# CircuitClockAutorouted.net
KiCad netlist of a schematic drawn in EAGLE
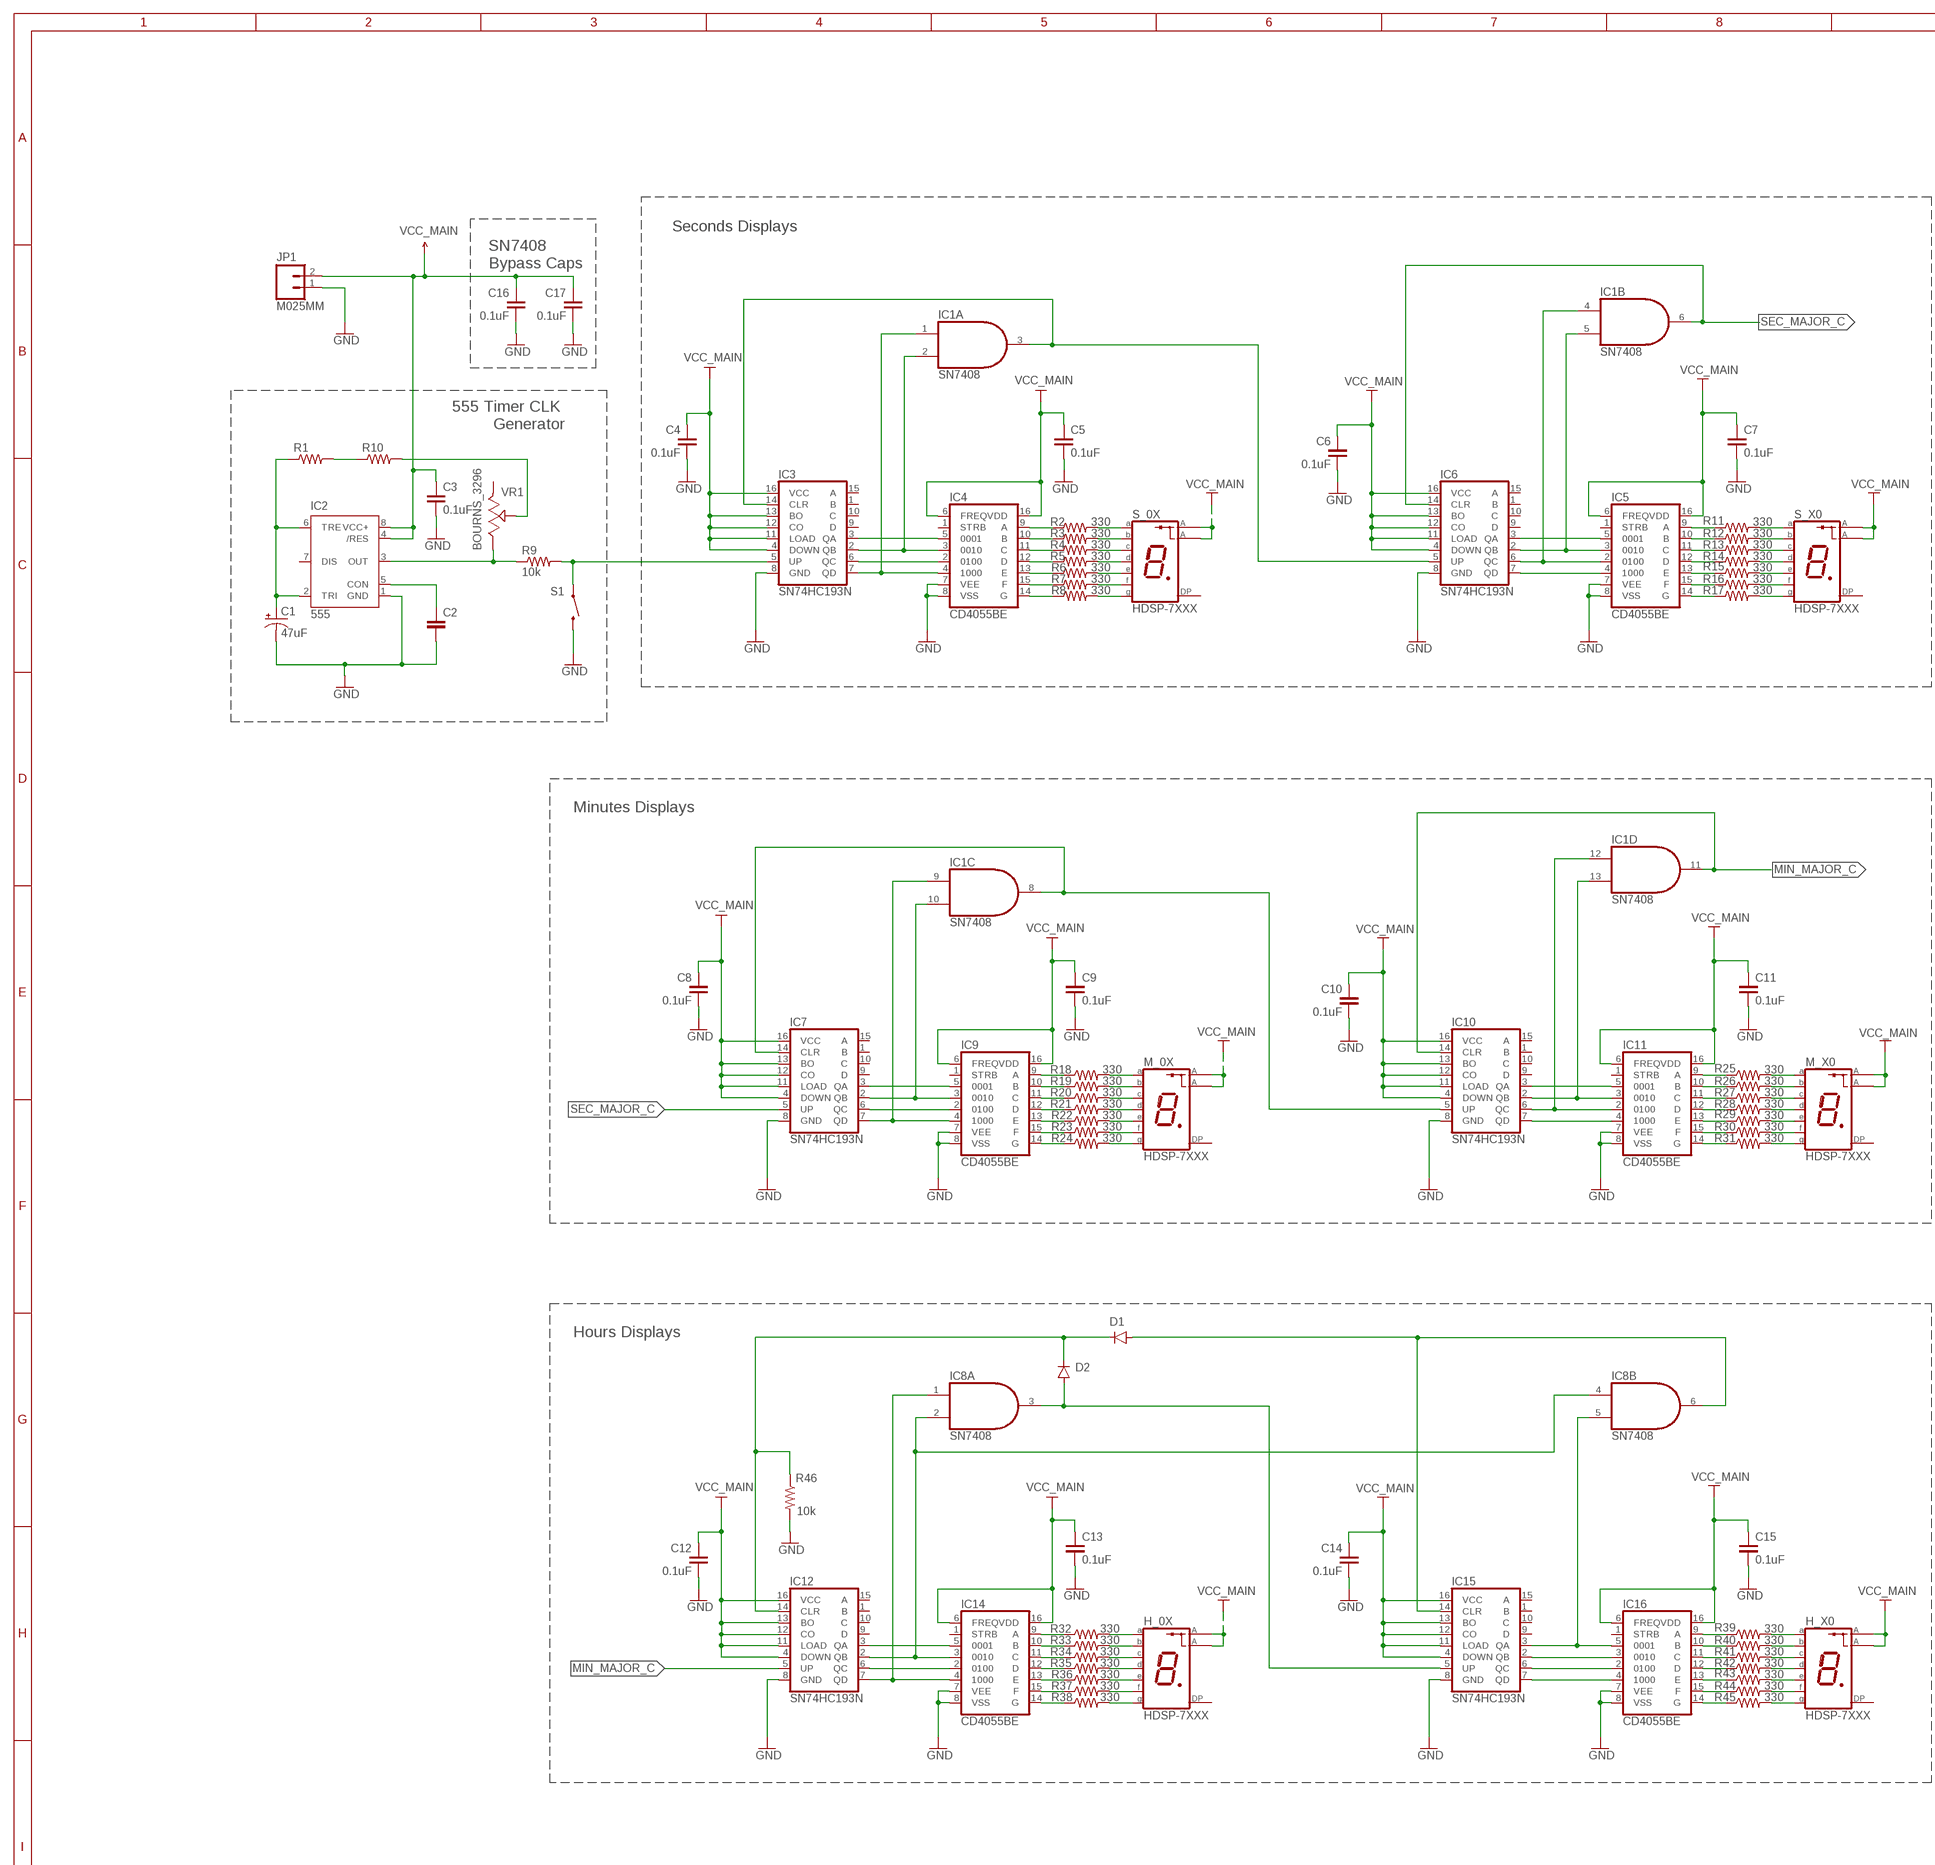
[diagram p0: schematic, sheet 1, part 1 of 2]
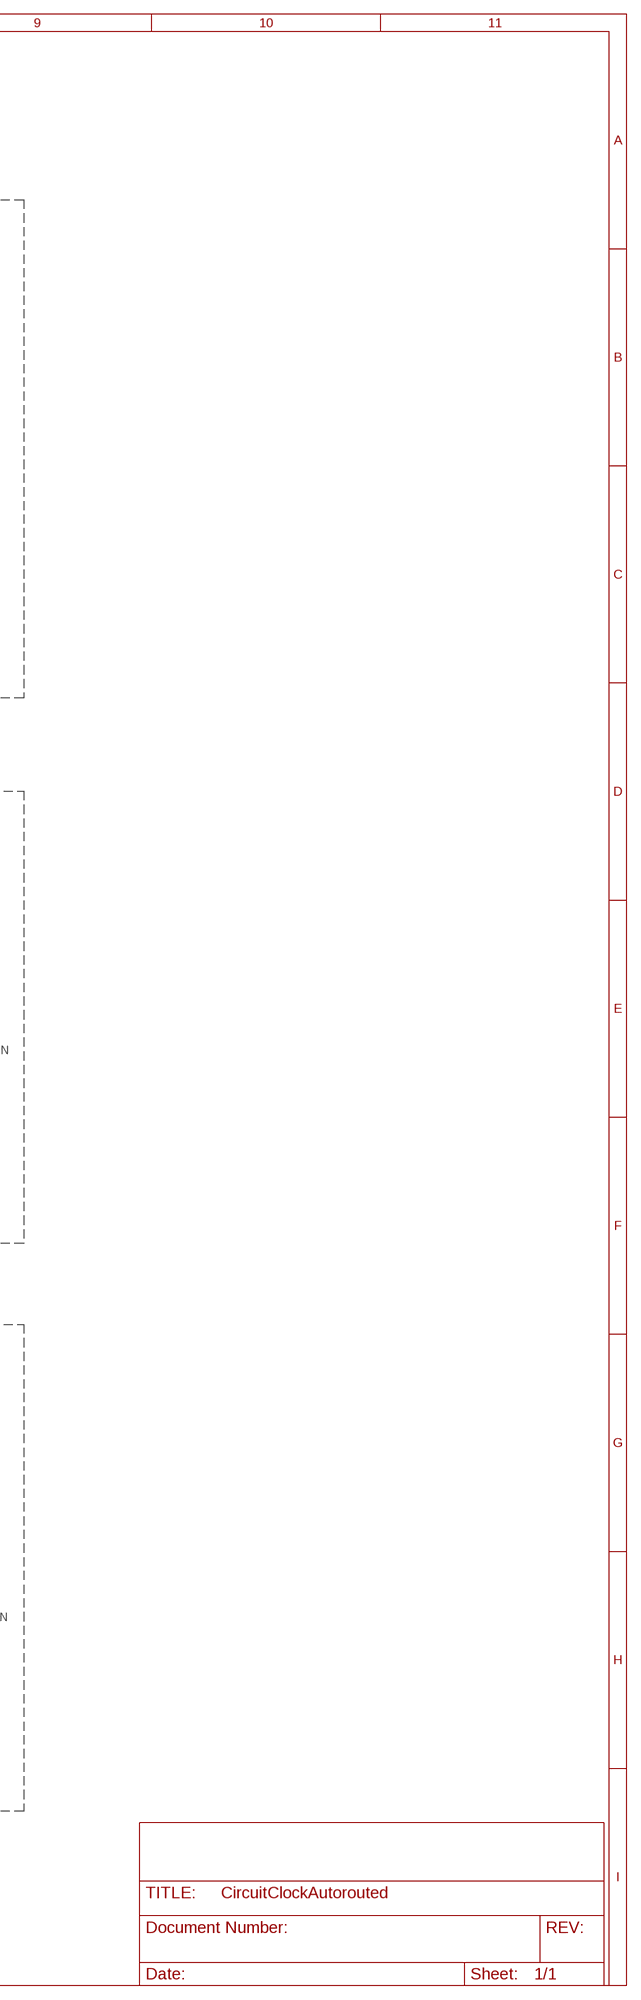
[diagram p1: schematic, sheet 1, part 2 of 2]

(export (version "E")
  (design (tool "Eeschema 10.0.6"))
  (components
    (comp (ref "C1")
      (value "47uF")
      (footprint "eagle-import:2.54MM_LEAD-6.3MM_DIA")
      (libsource (lib "eagle-import") (part "RADIAL_POL2.54MM_LEAD-6.3MM_DIA"))
    )
    (comp (ref "C2")
      (value "CAPPTH")
      (footprint "eagle-import:CAP-PTH-SMALL")
      (libsource (lib "eagle-import") (part "CAPPTH"))
    )
    (comp (ref "C3")
      (value "0.1uF")
      (footprint "eagle-import:2.54MM_LEAD")
      (libsource (lib "eagle-import") (part "NON_POL_2.5MM"))
    )
    (comp (ref "C4")
      (value "0.1uF")
      (footprint "eagle-import:2.54MM_LEAD")
      (libsource (lib "eagle-import") (part "NON_POL_2.5MM"))
    )
    (comp (ref "C5")
      (value "0.1uF")
      (footprint "eagle-import:2.54MM_LEAD")
      (libsource (lib "eagle-import") (part "NON_POL_2.5MM"))
    )
    (comp (ref "C6")
      (value "0.1uF")
      (footprint "eagle-import:2.54MM_LEAD")
      (libsource (lib "eagle-import") (part "NON_POL_2.5MM"))
    )
    (comp (ref "C7")
      (value "0.1uF")
      (footprint "eagle-import:2.54MM_LEAD")
      (libsource (lib "eagle-import") (part "NON_POL_2.5MM"))
    )
    (comp (ref "C8")
      (value "0.1uF")
      (footprint "eagle-import:2.54MM_LEAD")
      (libsource (lib "eagle-import") (part "NON_POL_2.5MM"))
    )
    (comp (ref "C9")
      (value "0.1uF")
      (footprint "eagle-import:2.54MM_LEAD")
      (libsource (lib "eagle-import") (part "NON_POL_2.5MM"))
    )
    (comp (ref "C10")
      (value "0.1uF")
      (footprint "eagle-import:2.54MM_LEAD")
      (libsource (lib "eagle-import") (part "NON_POL_2.5MM"))
    )
    (comp (ref "C11")
      (value "0.1uF")
      (footprint "eagle-import:2.54MM_LEAD")
      (libsource (lib "eagle-import") (part "NON_POL_2.5MM"))
    )
    (comp (ref "C12")
      (value "0.1uF")
      (footprint "eagle-import:2.54MM_LEAD")
      (libsource (lib "eagle-import") (part "NON_POL_2.5MM"))
    )
    (comp (ref "C13")
      (value "0.1uF")
      (footprint "eagle-import:2.54MM_LEAD")
      (libsource (lib "eagle-import") (part "NON_POL_2.5MM"))
    )
    (comp (ref "C14")
      (value "0.1uF")
      (footprint "eagle-import:2.54MM_LEAD")
      (libsource (lib "eagle-import") (part "NON_POL_2.5MM"))
    )
    (comp (ref "C15")
      (value "0.1uF")
      (footprint "eagle-import:2.54MM_LEAD")
      (libsource (lib "eagle-import") (part "NON_POL_2.5MM"))
    )
    (comp (ref "C16")
      (value "0.1uF")
      (footprint "eagle-import:2.54MM_LEAD")
      (libsource (lib "eagle-import") (part "NON_POL_2.5MM"))
    )
    (comp (ref "C17")
      (value "0.1uF")
      (footprint "eagle-import:2.54MM_LEAD")
      (libsource (lib "eagle-import") (part "NON_POL_2.5MM"))
    )
    (comp (ref "D1")
      (value "THROUGH_HOLE_DO-35")
      (footprint "eagle-import:DO35-10")
      (libsource (lib "eagle-import") (part "THROUGH_HOLE_DO-35"))
    )
    (comp (ref "D2")
      (value "THROUGH_HOLE_DO-35")
      (footprint "eagle-import:DO35-10")
      (libsource (lib "eagle-import") (part "THROUGH_HOLE_DO-35"))
    )
    (comp (ref "H_0X")
      (value "HDSP-7XXX")
      (footprint "eagle-import:HDSP-7XXX")
      (libsource (lib "eagle-import") (part "HDSP-7XXX"))
    )
    (comp (ref "H_X0")
      (value "HDSP-7XXX")
      (footprint "eagle-import:HDSP-7XXX")
      (libsource (lib "eagle-import") (part "HDSP-7XXX"))
    )
    (comp (ref "IC1")
      (value "SN7408")
      (footprint "eagle-import:DIL14")
      (libsource (lib "eagle-import") (part "7408NS"))
    )
    (comp (ref "IC2")
      (value "555")
      (footprint "eagle-import:DIP08-KIT")
      (libsource (lib "eagle-import") (part "555KIT"))
    )
    (comp (ref "IC3")
      (value "SN74HC193N")
      (footprint "eagle-import:DIL16")
      (libsource (lib "eagle-import") (part "SN74HC193N"))
    )
    (comp (ref "IC4")
      (value "CD4055BE")
      (footprint "eagle-import:DIL16")
      (libsource (lib "eagle-import") (part "CD4055BE"))
    )
    (comp (ref "IC5")
      (value "CD4055BE")
      (footprint "eagle-import:DIL16")
      (libsource (lib "eagle-import") (part "CD4055BE"))
    )
    (comp (ref "IC6")
      (value "SN74HC193N")
      (footprint "eagle-import:DIL16")
      (libsource (lib "eagle-import") (part "SN74HC193N"))
    )
    (comp (ref "IC7")
      (value "SN74HC193N")
      (footprint "eagle-import:DIL16")
      (libsource (lib "eagle-import") (part "SN74HC193N"))
    )
    (comp (ref "IC8")
      (value "SN7408")
      (footprint "eagle-import:DIL14")
      (libsource (lib "eagle-import") (part "7408NS"))
    )
    (comp (ref "IC9")
      (value "CD4055BE")
      (footprint "eagle-import:DIL16")
      (libsource (lib "eagle-import") (part "CD4055BE"))
    )
    (comp (ref "IC10")
      (value "SN74HC193N")
      (footprint "eagle-import:DIL16")
      (libsource (lib "eagle-import") (part "SN74HC193N"))
    )
    (comp (ref "IC11")
      (value "CD4055BE")
      (footprint "eagle-import:DIL16")
      (libsource (lib "eagle-import") (part "CD4055BE"))
    )
    (comp (ref "IC12")
      (value "SN74HC193N")
      (footprint "eagle-import:DIL16")
      (libsource (lib "eagle-import") (part "SN74HC193N"))
    )
    (comp (ref "IC14")
      (value "CD4055BE")
      (footprint "eagle-import:DIL16")
      (libsource (lib "eagle-import") (part "CD4055BE"))
    )
    (comp (ref "IC15")
      (value "SN74HC193N")
      (footprint "eagle-import:DIL16")
      (libsource (lib "eagle-import") (part "SN74HC193N"))
    )
    (comp (ref "IC16")
      (value "CD4055BE")
      (footprint "eagle-import:DIL16")
      (libsource (lib "eagle-import") (part "CD4055BE"))
    )
    (comp (ref "JP1")
      (value "M025MM")
      (footprint "eagle-import:SCREWTERMINAL-5MM-2")
      (libsource (lib "eagle-import") (part "M025MM"))
    )
    (comp (ref "M_0X")
      (value "HDSP-7XXX")
      (footprint "eagle-import:HDSP-7XXX")
      (libsource (lib "eagle-import") (part "HDSP-7XXX"))
    )
    (comp (ref "M_X0")
      (value "HDSP-7XXX")
      (footprint "eagle-import:HDSP-7XXX")
      (libsource (lib "eagle-import") (part "HDSP-7XXX"))
    )
    (comp (ref "R1")
      (value "RESISTORAXIAL-0.3")
      (footprint "eagle-import:AXIAL-0.3")
      (libsource (lib "eagle-import") (part "RESISTORAXIAL-0.3"))
    )
    (comp (ref "R2")
      (value "330")
      (footprint "eagle-import:1_4W_0.3")
      (libsource (lib "eagle-import") (part "THROUGH_HOLE_1/4W_0.3"))
    )
    (comp (ref "R3")
      (value "330")
      (footprint "eagle-import:1_4W_0.3")
      (libsource (lib "eagle-import") (part "THROUGH_HOLE_1/4W_0.3"))
    )
    (comp (ref "R4")
      (value "330")
      (footprint "eagle-import:1_4W_0.3")
      (libsource (lib "eagle-import") (part "THROUGH_HOLE_1/4W_0.3"))
    )
    (comp (ref "R5")
      (value "330")
      (footprint "eagle-import:1_4W_0.3")
      (libsource (lib "eagle-import") (part "THROUGH_HOLE_1/4W_0.3"))
    )
    (comp (ref "R6")
      (value "330")
      (footprint "eagle-import:1_4W_0.3")
      (libsource (lib "eagle-import") (part "THROUGH_HOLE_1/4W_0.3"))
    )
    (comp (ref "R7")
      (value "330")
      (footprint "eagle-import:1_4W_0.3")
      (libsource (lib "eagle-import") (part "THROUGH_HOLE_1/4W_0.3"))
    )
    (comp (ref "R8")
      (value "330")
      (footprint "eagle-import:1_4W_0.3")
      (libsource (lib "eagle-import") (part "THROUGH_HOLE_1/4W_0.3"))
    )
    (comp (ref "R9")
      (value "10k")
      (footprint "eagle-import:AXIAL-0.3")
      (libsource (lib "eagle-import") (part "RESISTORAXIAL-0.3"))
    )
    (comp (ref "R10")
      (value "RESISTORAXIAL-0.3")
      (footprint "eagle-import:AXIAL-0.3")
      (libsource (lib "eagle-import") (part "RESISTORAXIAL-0.3"))
    )
    (comp (ref "R11")
      (value "330")
      (footprint "eagle-import:1_4W_0.3")
      (libsource (lib "eagle-import") (part "THROUGH_HOLE_1/4W_0.3"))
    )
    (comp (ref "R12")
      (value "330")
      (footprint "eagle-import:1_4W_0.3")
      (libsource (lib "eagle-import") (part "THROUGH_HOLE_1/4W_0.3"))
    )
    (comp (ref "R13")
      (value "330")
      (footprint "eagle-import:1_4W_0.3")
      (libsource (lib "eagle-import") (part "THROUGH_HOLE_1/4W_0.3"))
    )
    (comp (ref "R14")
      (value "330")
      (footprint "eagle-import:1_4W_0.3")
      (libsource (lib "eagle-import") (part "THROUGH_HOLE_1/4W_0.3"))
    )
    (comp (ref "R15")
      (value "330")
      (footprint "eagle-import:1_4W_0.3")
      (libsource (lib "eagle-import") (part "THROUGH_HOLE_1/4W_0.3"))
    )
    (comp (ref "R16")
      (value "330")
      (footprint "eagle-import:1_4W_0.3")
      (libsource (lib "eagle-import") (part "THROUGH_HOLE_1/4W_0.3"))
    )
    (comp (ref "R17")
      (value "330")
      (footprint "eagle-import:1_4W_0.3")
      (libsource (lib "eagle-import") (part "THROUGH_HOLE_1/4W_0.3"))
    )
    (comp (ref "R18")
      (value "330")
      (footprint "eagle-import:1_4W_0.3")
      (libsource (lib "eagle-import") (part "THROUGH_HOLE_1/4W_0.3"))
    )
    (comp (ref "R19")
      (value "330")
      (footprint "eagle-import:1_4W_0.3")
      (libsource (lib "eagle-import") (part "THROUGH_HOLE_1/4W_0.3"))
    )
    (comp (ref "R20")
      (value "330")
      (footprint "eagle-import:1_4W_0.3")
      (libsource (lib "eagle-import") (part "THROUGH_HOLE_1/4W_0.3"))
    )
    (comp (ref "R21")
      (value "330")
      (footprint "eagle-import:1_4W_0.3")
      (libsource (lib "eagle-import") (part "THROUGH_HOLE_1/4W_0.3"))
    )
    (comp (ref "R22")
      (value "330")
      (footprint "eagle-import:1_4W_0.3")
      (libsource (lib "eagle-import") (part "THROUGH_HOLE_1/4W_0.3"))
    )
    (comp (ref "R23")
      (value "330")
      (footprint "eagle-import:1_4W_0.3")
      (libsource (lib "eagle-import") (part "THROUGH_HOLE_1/4W_0.3"))
    )
    (comp (ref "R24")
      (value "330")
      (footprint "eagle-import:1_4W_0.3")
      (libsource (lib "eagle-import") (part "THROUGH_HOLE_1/4W_0.3"))
    )
    (comp (ref "R25")
      (value "330")
      (footprint "eagle-import:1_4W_0.3")
      (libsource (lib "eagle-import") (part "THROUGH_HOLE_1/4W_0.3"))
    )
    (comp (ref "R26")
      (value "330")
      (footprint "eagle-import:1_4W_0.3")
      (libsource (lib "eagle-import") (part "THROUGH_HOLE_1/4W_0.3"))
    )
    (comp (ref "R27")
      (value "330")
      (footprint "eagle-import:1_4W_0.3")
      (libsource (lib "eagle-import") (part "THROUGH_HOLE_1/4W_0.3"))
    )
    (comp (ref "R28")
      (value "330")
      (footprint "eagle-import:1_4W_0.3")
      (libsource (lib "eagle-import") (part "THROUGH_HOLE_1/4W_0.3"))
    )
    (comp (ref "R29")
      (value "330")
      (footprint "eagle-import:1_4W_0.3")
      (libsource (lib "eagle-import") (part "THROUGH_HOLE_1/4W_0.3"))
    )
    (comp (ref "R30")
      (value "330")
      (footprint "eagle-import:1_4W_0.3")
      (libsource (lib "eagle-import") (part "THROUGH_HOLE_1/4W_0.3"))
    )
    (comp (ref "R31")
      (value "330")
      (footprint "eagle-import:1_4W_0.3")
      (libsource (lib "eagle-import") (part "THROUGH_HOLE_1/4W_0.3"))
    )
    (comp (ref "R32")
      (value "330")
      (footprint "eagle-import:1_4W_0.3")
      (libsource (lib "eagle-import") (part "THROUGH_HOLE_1/4W_0.3"))
    )
    (comp (ref "R33")
      (value "330")
      (footprint "eagle-import:1_4W_0.3")
      (libsource (lib "eagle-import") (part "THROUGH_HOLE_1/4W_0.3"))
    )
    (comp (ref "R34")
      (value "330")
      (footprint "eagle-import:1_4W_0.3")
      (libsource (lib "eagle-import") (part "THROUGH_HOLE_1/4W_0.3"))
    )
    (comp (ref "R35")
      (value "330")
      (footprint "eagle-import:1_4W_0.3")
      (libsource (lib "eagle-import") (part "THROUGH_HOLE_1/4W_0.3"))
    )
    (comp (ref "R36")
      (value "330")
      (footprint "eagle-import:1_4W_0.3")
      (libsource (lib "eagle-import") (part "THROUGH_HOLE_1/4W_0.3"))
    )
    (comp (ref "R37")
      (value "330")
      (footprint "eagle-import:1_4W_0.3")
      (libsource (lib "eagle-import") (part "THROUGH_HOLE_1/4W_0.3"))
    )
    (comp (ref "R38")
      (value "330")
      (footprint "eagle-import:1_4W_0.3")
      (libsource (lib "eagle-import") (part "THROUGH_HOLE_1/4W_0.3"))
    )
    (comp (ref "R39")
      (value "330")
      (footprint "eagle-import:1_4W_0.3")
      (libsource (lib "eagle-import") (part "THROUGH_HOLE_1/4W_0.3"))
    )
    (comp (ref "R40")
      (value "330")
      (footprint "eagle-import:1_4W_0.3")
      (libsource (lib "eagle-import") (part "THROUGH_HOLE_1/4W_0.3"))
    )
    (comp (ref "R41")
      (value "330")
      (footprint "eagle-import:1_4W_0.3")
      (libsource (lib "eagle-import") (part "THROUGH_HOLE_1/4W_0.3"))
    )
    (comp (ref "R42")
      (value "330")
      (footprint "eagle-import:1_4W_0.3")
      (libsource (lib "eagle-import") (part "THROUGH_HOLE_1/4W_0.3"))
    )
    (comp (ref "R43")
      (value "330")
      (footprint "eagle-import:1_4W_0.3")
      (libsource (lib "eagle-import") (part "THROUGH_HOLE_1/4W_0.3"))
    )
    (comp (ref "R44")
      (value "330")
      (footprint "eagle-import:1_4W_0.3")
      (libsource (lib "eagle-import") (part "THROUGH_HOLE_1/4W_0.3"))
    )
    (comp (ref "R45")
      (value "330")
      (footprint "eagle-import:1_4W_0.3")
      (libsource (lib "eagle-import") (part "THROUGH_HOLE_1/4W_0.3"))
    )
    (comp (ref "R46")
      (value "10k")
      (footprint "eagle-import:1_4W_0.3")
      (libsource (lib "eagle-import") (part "THROUGH_HOLE_1/4W_0.3"))
    )
    (comp (ref "S1")
      (value "SWITCH-MOMENTARY-2PTH")
      (footprint "eagle-import:TACTILE-PTH")
      (libsource (lib "eagle-import") (part "SWITCH-MOMENTARY-2PTH"))
    )
    (comp (ref "S_0X")
      (value "HDSP-7XXX")
      (footprint "eagle-import:HDSP-7XXX")
      (libsource (lib "eagle-import") (part "HDSP-7XXX"))
    )
    (comp (ref "S_X0")
      (value "HDSP-7XXX")
      (footprint "eagle-import:HDSP-7XXX")
      (libsource (lib "eagle-import") (part "HDSP-7XXX"))
    )
    (comp (ref "VR1")
      (value "BOURNS_3296")
      (footprint "eagle-import:3296")
      (libsource (lib "eagle-import") (part "BOURNS_3296"))
    )
  )
  (nets
    (net (code "1") (name "GND") (class "Default")
      (node (ref "C1") (pin "-") (pinfunction "-_-") (pintype "passive"))
      (node (ref "C10") (pin "2") (pinfunction "2_2") (pintype "passive"))
      (node (ref "C11") (pin "2") (pinfunction "2_2") (pintype "passive"))
      (node (ref "C12") (pin "2") (pinfunction "2_2") (pintype "passive"))
      (node (ref "C13") (pin "2") (pinfunction "2_2") (pintype "passive"))
      (node (ref "C14") (pin "2") (pinfunction "2_2") (pintype "passive"))
      (node (ref "C15") (pin "2") (pinfunction "2_2") (pintype "passive"))
      (node (ref "C16") (pin "2") (pinfunction "2_2") (pintype "passive"))
      (node (ref "C17") (pin "2") (pinfunction "2_2") (pintype "passive"))
      (node (ref "C2") (pin "2") (pinfunction "2_2") (pintype "passive"))
      (node (ref "C3") (pin "2") (pinfunction "2_2") (pintype "passive"))
      (node (ref "C4") (pin "2") (pinfunction "2_2") (pintype "passive"))
      (node (ref "C5") (pin "2") (pinfunction "2_2") (pintype "passive"))
      (node (ref "C6") (pin "2") (pinfunction "2_2") (pintype "passive"))
      (node (ref "C7") (pin "2") (pinfunction "2_2") (pintype "passive"))
      (node (ref "C8") (pin "2") (pinfunction "2_2") (pintype "passive"))
      (node (ref "C9") (pin "2") (pinfunction "2_2") (pintype "passive"))
      (node (ref "IC10") (pin "8") (pinfunction "GND_8") (pintype "power_in"))
      (node (ref "IC11") (pin "7") (pinfunction "VEE_7") (pintype "bidirectional"))
      (node (ref "IC11") (pin "8") (pinfunction "VSS_8") (pintype "power_in"))
      (node (ref "IC12") (pin "8") (pinfunction "GND_8") (pintype "power_in"))
      (node (ref "IC14") (pin "7") (pinfunction "VEE_7") (pintype "bidirectional"))
      (node (ref "IC14") (pin "8") (pinfunction "VSS_8") (pintype "power_in"))
      (node (ref "IC15") (pin "8") (pinfunction "GND_8") (pintype "power_in"))
      (node (ref "IC16") (pin "7") (pinfunction "VEE_7") (pintype "bidirectional"))
      (node (ref "IC16") (pin "8") (pinfunction "VSS_8") (pintype "power_in"))
      (node (ref "IC2") (pin "1") (pinfunction "GND_1") (pintype "power_in"))
      (node (ref "IC3") (pin "8") (pinfunction "GND_8") (pintype "power_in"))
      (node (ref "IC4") (pin "7") (pinfunction "VEE_7") (pintype "bidirectional"))
      (node (ref "IC4") (pin "8") (pinfunction "VSS_8") (pintype "power_in"))
      (node (ref "IC5") (pin "7") (pinfunction "VEE_7") (pintype "bidirectional"))
      (node (ref "IC5") (pin "8") (pinfunction "VSS_8") (pintype "power_in"))
      (node (ref "IC6") (pin "8") (pinfunction "GND_8") (pintype "power_in"))
      (node (ref "IC7") (pin "8") (pinfunction "GND_8") (pintype "power_in"))
      (node (ref "IC9") (pin "7") (pinfunction "VEE_7") (pintype "bidirectional"))
      (node (ref "IC9") (pin "8") (pinfunction "VSS_8") (pintype "power_in"))
      (node (ref "JP1") (pin "1") (pinfunction "1_1") (pintype "passive"))
      (node (ref "R46") (pin "P$2") (pinfunction "2_P$2") (pintype "passive"))
      (node (ref "S1") (pin "3") (pinfunction "2_3") (pintype "passive"))
    )
    (net (code "2") (name "MIN_MAJOR_C") (class "Default")
      (node (ref "IC1") (pin "11") (pinfunction "O_11") (pintype "output"))
      (node (ref "IC10") (pin "14") (pinfunction "CLR_14") (pintype "bidirectional"))
      (node (ref "IC12") (pin "5") (pinfunction "UP_5") (pintype "bidirectional"))
    )
    (net (code "3") (name "Net-(H_0X-B)") (class "Default")
      (node (ref "H_0X") (pin "P$9") (pinfunction "B_P$9") (pintype "passive"))
      (node (ref "R33") (pin "P$2") (pinfunction "2_P$2") (pintype "passive"))
    )
    (net (code "4") (name "Net-(H_0X-C)") (class "Default")
      (node (ref "H_0X") (pin "P$8") (pinfunction "C_P$8") (pintype "passive"))
      (node (ref "R34") (pin "P$2") (pinfunction "2_P$2") (pintype "passive"))
    )
    (net (code "5") (name "Net-(H_0X-D)") (class "Default")
      (node (ref "H_0X") (pin "P$5") (pinfunction "D_P$5") (pintype "passive"))
      (node (ref "R35") (pin "P$2") (pinfunction "2_P$2") (pintype "passive"))
    )
    (net (code "6") (name "Net-(H_0X-E)") (class "Default")
      (node (ref "H_0X") (pin "P$4") (pinfunction "E_P$4") (pintype "passive"))
      (node (ref "R36") (pin "P$2") (pinfunction "2_P$2") (pintype "passive"))
    )
    (net (code "7") (name "Net-(H_0X-F)") (class "Default")
      (node (ref "H_0X") (pin "P$2") (pinfunction "F_P$2") (pintype "passive"))
      (node (ref "R37") (pin "P$2") (pinfunction "2_P$2") (pintype "passive"))
    )
    (net (code "8") (name "Net-(H_0X-G)") (class "Default")
      (node (ref "H_0X") (pin "P$3") (pinfunction "G_P$3") (pintype "passive"))
      (node (ref "R38") (pin "P$2") (pinfunction "2_P$2") (pintype "passive"))
    )
    (net (code "9") (name "Net-(H_X0-B)") (class "Default")
      (node (ref "H_X0") (pin "P$9") (pinfunction "B_P$9") (pintype "passive"))
      (node (ref "R40") (pin "P$2") (pinfunction "2_P$2") (pintype "passive"))
    )
    (net (code "10") (name "Net-(H_X0-C)") (class "Default")
      (node (ref "H_X0") (pin "P$8") (pinfunction "C_P$8") (pintype "passive"))
      (node (ref "R41") (pin "P$2") (pinfunction "2_P$2") (pintype "passive"))
    )
    (net (code "11") (name "Net-(H_X0-D)") (class "Default")
      (node (ref "H_X0") (pin "P$5") (pinfunction "D_P$5") (pintype "passive"))
      (node (ref "R42") (pin "P$2") (pinfunction "2_P$2") (pintype "passive"))
    )
    (net (code "12") (name "Net-(H_X0-E)") (class "Default")
      (node (ref "H_X0") (pin "P$4") (pinfunction "E_P$4") (pintype "passive"))
      (node (ref "R43") (pin "P$2") (pinfunction "2_P$2") (pintype "passive"))
    )
    (net (code "13") (name "Net-(H_X0-F)") (class "Default")
      (node (ref "H_X0") (pin "P$2") (pinfunction "F_P$2") (pintype "passive"))
      (node (ref "R44") (pin "P$2") (pinfunction "2_P$2") (pintype "passive"))
    )
    (net (code "14") (name "Net-(H_X0-G)") (class "Default")
      (node (ref "H_X0") (pin "P$3") (pinfunction "G_P$3") (pintype "passive"))
      (node (ref "R45") (pin "P$2") (pinfunction "2_P$2") (pintype "passive"))
    )
    (net (code "15") (name "Net-(IC1A-I0)") (class "Default")
      (node (ref "IC1") (pin "1") (pinfunction "I0_1") (pintype "input"))
      (node (ref "IC3") (pin "7") (pinfunction "QD_7") (pintype "bidirectional"))
      (node (ref "IC4") (pin "4") (pinfunction "1000_4") (pintype "bidirectional"))
    )
    (net (code "16") (name "Net-(IC1A-I1)") (class "Default")
      (node (ref "IC1") (pin "2") (pinfunction "I1_2") (pintype "input"))
      (node (ref "IC3") (pin "2") (pinfunction "QB_2") (pintype "bidirectional"))
      (node (ref "IC4") (pin "3") (pinfunction "0010_3") (pintype "input"))
    )
    (net (code "17") (name "Net-(IC1A-O)") (class "Default")
      (node (ref "IC1") (pin "3") (pinfunction "O_3") (pintype "output"))
      (node (ref "IC3") (pin "14") (pinfunction "CLR_14") (pintype "bidirectional"))
      (node (ref "IC6") (pin "5") (pinfunction "UP_5") (pintype "bidirectional"))
    )
    (net (code "18") (name "Net-(IC1B-I0)") (class "Default")
      (node (ref "IC1") (pin "4") (pinfunction "I0_4") (pintype "input"))
      (node (ref "IC5") (pin "2") (pinfunction "0100_2") (pintype "input"))
      (node (ref "IC6") (pin "6") (pinfunction "QC_6") (pintype "bidirectional"))
    )
    (net (code "19") (name "Net-(IC1B-I1)") (class "Default")
      (node (ref "IC1") (pin "5") (pinfunction "I1_5") (pintype "input"))
      (node (ref "IC5") (pin "3") (pinfunction "0010_3") (pintype "input"))
      (node (ref "IC6") (pin "2") (pinfunction "QB_2") (pintype "bidirectional"))
    )
    (net (code "20") (name "Net-(IC1C-I0)") (class "Default")
      (node (ref "IC1") (pin "9") (pinfunction "I0_9") (pintype "input"))
      (node (ref "IC7") (pin "7") (pinfunction "QD_7") (pintype "bidirectional"))
      (node (ref "IC9") (pin "4") (pinfunction "1000_4") (pintype "bidirectional"))
    )
    (net (code "21") (name "Net-(IC1C-I1)") (class "Default")
      (node (ref "IC1") (pin "10") (pinfunction "I1_10") (pintype "input"))
      (node (ref "IC7") (pin "2") (pinfunction "QB_2") (pintype "bidirectional"))
      (node (ref "IC9") (pin "3") (pinfunction "0010_3") (pintype "input"))
    )
    (net (code "22") (name "Net-(IC2-CON)") (class "Default")
      (node (ref "C2") (pin "1") (pinfunction "1_1") (pintype "passive"))
      (node (ref "IC2") (pin "5") (pinfunction "CON_5") (pintype "input"))
    )
    (net (code "23") (name "Net-(IC2-OUT)") (class "Default")
      (node (ref "IC2") (pin "3") (pinfunction "OUT_3") (pintype "output"))
      (node (ref "R9") (pin "P$1") (pinfunction "1_P$1") (pintype "passive"))
      (node (ref "VR1") (pin "1") (pinfunction "A_1") (pintype "passive"))
    )
    (net (code "24") (name "Net-(IC2-TRE)") (class "Default")
      (node (ref "C1") (pin "+") (pinfunction "+_+") (pintype "passive"))
      (node (ref "IC2") (pin "2") (pinfunction "TRI_2") (pintype "input"))
      (node (ref "IC2") (pin "6") (pinfunction "TRE_6") (pintype "input"))
      (node (ref "R1") (pin "P$1") (pinfunction "1_P$1") (pintype "passive"))
    )
    (net (code "25") (name "Net-(IC3-QA)") (class "Default")
      (node (ref "IC3") (pin "3") (pinfunction "QA_3") (pintype "bidirectional"))
      (node (ref "IC4") (pin "5") (pinfunction "0001_5") (pintype "input"))
    )
    (net (code "26") (name "Net-(IC3-QC)") (class "Default")
      (node (ref "IC3") (pin "6") (pinfunction "QC_6") (pintype "bidirectional"))
      (node (ref "IC4") (pin "2") (pinfunction "0100_2") (pintype "input"))
    )
    (net (code "27") (name "Net-(IC3-UP)") (class "Default")
      (node (ref "IC3") (pin "5") (pinfunction "UP_5") (pintype "bidirectional"))
      (node (ref "R9") (pin "P$2") (pinfunction "2_P$2") (pintype "passive"))
      (node (ref "S1") (pin "1") (pinfunction "1_1") (pintype "passive"))
    )
    (net (code "28") (name "Net-(IC4-A)") (class "Default")
      (node (ref "IC4") (pin "9") (pinfunction "A_9") (pintype "bidirectional"))
      (node (ref "R2") (pin "P$1") (pinfunction "1_P$1") (pintype "passive"))
    )
    (net (code "29") (name "Net-(IC4-B)") (class "Default")
      (node (ref "IC4") (pin "10") (pinfunction "B_10") (pintype "bidirectional"))
      (node (ref "R3") (pin "P$1") (pinfunction "1_P$1") (pintype "passive"))
    )
    (net (code "30") (name "Net-(IC4-C)") (class "Default")
      (node (ref "IC4") (pin "11") (pinfunction "C_11") (pintype "bidirectional"))
      (node (ref "R4") (pin "P$1") (pinfunction "1_P$1") (pintype "passive"))
    )
    (net (code "31") (name "Net-(IC4-D)") (class "Default")
      (node (ref "IC4") (pin "12") (pinfunction "D_12") (pintype "bidirectional"))
      (node (ref "R5") (pin "P$1") (pinfunction "1_P$1") (pintype "passive"))
    )
    (net (code "32") (name "Net-(IC4-E)") (class "Default")
      (node (ref "IC4") (pin "13") (pinfunction "E_13") (pintype "bidirectional"))
      (node (ref "R6") (pin "P$1") (pinfunction "1_P$1") (pintype "passive"))
    )
    (net (code "33") (name "Net-(IC4-F)") (class "Default")
      (node (ref "IC4") (pin "15") (pinfunction "F_15") (pintype "bidirectional"))
      (node (ref "R7") (pin "P$1") (pinfunction "1_P$1") (pintype "passive"))
    )
    (net (code "34") (name "Net-(IC4-G)") (class "Default")
      (node (ref "IC4") (pin "14") (pinfunction "G_14") (pintype "bidirectional"))
      (node (ref "R8") (pin "P$1") (pinfunction "1_P$1") (pintype "passive"))
    )
    (net (code "35") (name "Net-(IC5-0001)") (class "Default")
      (node (ref "IC5") (pin "5") (pinfunction "0001_5") (pintype "input"))
      (node (ref "IC6") (pin "3") (pinfunction "QA_3") (pintype "bidirectional"))
    )
    (net (code "36") (name "Net-(IC5-1000)") (class "Default")
      (node (ref "IC5") (pin "4") (pinfunction "1000_4") (pintype "bidirectional"))
      (node (ref "IC6") (pin "7") (pinfunction "QD_7") (pintype "bidirectional"))
    )
    (net (code "37") (name "Net-(IC5-A)") (class "Default")
      (node (ref "IC5") (pin "9") (pinfunction "A_9") (pintype "bidirectional"))
      (node (ref "R11") (pin "P$1") (pinfunction "1_P$1") (pintype "passive"))
    )
    (net (code "38") (name "Net-(IC5-B)") (class "Default")
      (node (ref "IC5") (pin "10") (pinfunction "B_10") (pintype "bidirectional"))
      (node (ref "R12") (pin "P$1") (pinfunction "1_P$1") (pintype "passive"))
    )
    (net (code "39") (name "Net-(IC5-C)") (class "Default")
      (node (ref "IC5") (pin "11") (pinfunction "C_11") (pintype "bidirectional"))
      (node (ref "R13") (pin "P$1") (pinfunction "1_P$1") (pintype "passive"))
    )
    (net (code "40") (name "Net-(IC5-D)") (class "Default")
      (node (ref "IC5") (pin "12") (pinfunction "D_12") (pintype "bidirectional"))
      (node (ref "R14") (pin "P$1") (pinfunction "1_P$1") (pintype "passive"))
    )
    (net (code "41") (name "Net-(IC5-E)") (class "Default")
      (node (ref "IC5") (pin "13") (pinfunction "E_13") (pintype "bidirectional"))
      (node (ref "R15") (pin "P$1") (pinfunction "1_P$1") (pintype "passive"))
    )
    (net (code "42") (name "Net-(IC5-F)") (class "Default")
      (node (ref "IC5") (pin "15") (pinfunction "F_15") (pintype "bidirectional"))
      (node (ref "R16") (pin "P$1") (pinfunction "1_P$1") (pintype "passive"))
    )
    (net (code "43") (name "Net-(IC5-G)") (class "Default")
      (node (ref "IC5") (pin "14") (pinfunction "G_14") (pintype "bidirectional"))
      (node (ref "R17") (pin "P$1") (pinfunction "1_P$1") (pintype "passive"))
    )
    (net (code "44") (name "Net-(IC7-QA)") (class "Default")
      (node (ref "IC7") (pin "3") (pinfunction "QA_3") (pintype "bidirectional"))
      (node (ref "IC9") (pin "5") (pinfunction "0001_5") (pintype "input"))
    )
    (net (code "45") (name "Net-(IC7-QC)") (class "Default")
      (node (ref "IC7") (pin "6") (pinfunction "QC_6") (pintype "bidirectional"))
      (node (ref "IC9") (pin "2") (pinfunction "0100_2") (pintype "input"))
    )
    (net (code "46") (name "Net-(IC9-A)") (class "Default")
      (node (ref "IC9") (pin "9") (pinfunction "A_9") (pintype "bidirectional"))
      (node (ref "R18") (pin "P$1") (pinfunction "1_P$1") (pintype "passive"))
    )
    (net (code "47") (name "Net-(IC9-B)") (class "Default")
      (node (ref "IC9") (pin "10") (pinfunction "B_10") (pintype "bidirectional"))
      (node (ref "R19") (pin "P$1") (pinfunction "1_P$1") (pintype "passive"))
    )
    (net (code "48") (name "Net-(IC9-C)") (class "Default")
      (node (ref "IC9") (pin "11") (pinfunction "C_11") (pintype "bidirectional"))
      (node (ref "R20") (pin "P$1") (pinfunction "1_P$1") (pintype "passive"))
    )
    (net (code "49") (name "Net-(IC9-D)") (class "Default")
      (node (ref "IC9") (pin "12") (pinfunction "D_12") (pintype "bidirectional"))
      (node (ref "R21") (pin "P$1") (pinfunction "1_P$1") (pintype "passive"))
    )
    (net (code "50") (name "Net-(IC9-E)") (class "Default")
      (node (ref "IC9") (pin "13") (pinfunction "E_13") (pintype "bidirectional"))
      (node (ref "R22") (pin "P$1") (pinfunction "1_P$1") (pintype "passive"))
    )
    (net (code "51") (name "Net-(IC9-F)") (class "Default")
      (node (ref "IC9") (pin "15") (pinfunction "F_15") (pintype "bidirectional"))
      (node (ref "R23") (pin "P$1") (pinfunction "1_P$1") (pintype "passive"))
    )
    (net (code "52") (name "Net-(IC9-G)") (class "Default")
      (node (ref "IC9") (pin "14") (pinfunction "G_14") (pintype "bidirectional"))
      (node (ref "R24") (pin "P$1") (pinfunction "1_P$1") (pintype "passive"))
    )
    (net (code "53") (name "Net-(IC10-QA)") (class "Default")
      (node (ref "IC10") (pin "3") (pinfunction "QA_3") (pintype "bidirectional"))
      (node (ref "IC11") (pin "5") (pinfunction "0001_5") (pintype "input"))
    )
    (net (code "54") (name "Net-(IC10-QB)") (class "Default")
      (node (ref "IC1") (pin "13") (pinfunction "I1_13") (pintype "input"))
      (node (ref "IC10") (pin "2") (pinfunction "QB_2") (pintype "bidirectional"))
      (node (ref "IC11") (pin "3") (pinfunction "0010_3") (pintype "input"))
    )
    (net (code "55") (name "Net-(IC10-QC)") (class "Default")
      (node (ref "IC1") (pin "12") (pinfunction "I0_12") (pintype "input"))
      (node (ref "IC10") (pin "6") (pinfunction "QC_6") (pintype "bidirectional"))
      (node (ref "IC11") (pin "2") (pinfunction "0100_2") (pintype "input"))
    )
    (net (code "56") (name "Net-(IC10-QD)") (class "Default")
      (node (ref "IC10") (pin "7") (pinfunction "QD_7") (pintype "bidirectional"))
      (node (ref "IC11") (pin "4") (pinfunction "1000_4") (pintype "bidirectional"))
    )
    (net (code "57") (name "Net-(IC10-UP)") (class "Default")
      (node (ref "IC1") (pin "8") (pinfunction "O_8") (pintype "output"))
      (node (ref "IC10") (pin "5") (pinfunction "UP_5") (pintype "bidirectional"))
      (node (ref "IC7") (pin "14") (pinfunction "CLR_14") (pintype "bidirectional"))
    )
    (net (code "58") (name "Net-(IC11-A)") (class "Default")
      (node (ref "IC11") (pin "9") (pinfunction "A_9") (pintype "bidirectional"))
      (node (ref "R25") (pin "P$1") (pinfunction "1_P$1") (pintype "passive"))
    )
    (net (code "59") (name "Net-(IC11-B)") (class "Default")
      (node (ref "IC11") (pin "10") (pinfunction "B_10") (pintype "bidirectional"))
      (node (ref "R26") (pin "P$1") (pinfunction "1_P$1") (pintype "passive"))
    )
    (net (code "60") (name "Net-(IC11-C)") (class "Default")
      (node (ref "IC11") (pin "11") (pinfunction "C_11") (pintype "bidirectional"))
      (node (ref "R27") (pin "P$1") (pinfunction "1_P$1") (pintype "passive"))
    )
    (net (code "61") (name "Net-(IC11-D)") (class "Default")
      (node (ref "IC11") (pin "12") (pinfunction "D_12") (pintype "bidirectional"))
      (node (ref "R28") (pin "P$1") (pinfunction "1_P$1") (pintype "passive"))
    )
    (net (code "62") (name "Net-(IC11-E)") (class "Default")
      (node (ref "IC11") (pin "13") (pinfunction "E_13") (pintype "bidirectional"))
      (node (ref "R29") (pin "P$1") (pinfunction "1_P$1") (pintype "passive"))
    )
    (net (code "63") (name "Net-(IC11-F)") (class "Default")
      (node (ref "IC11") (pin "15") (pinfunction "F_15") (pintype "bidirectional"))
      (node (ref "R30") (pin "P$1") (pinfunction "1_P$1") (pintype "passive"))
    )
    (net (code "64") (name "Net-(IC11-G)") (class "Default")
      (node (ref "IC11") (pin "14") (pinfunction "G_14") (pintype "bidirectional"))
      (node (ref "R31") (pin "P$1") (pinfunction "1_P$1") (pintype "passive"))
    )
    (net (code "65") (name "Net-(IC12-CLR)") (class "Default")
      (node (ref "D1") (pin "C") (pinfunction "C_C") (pintype "passive"))
      (node (ref "D2") (pin "C") (pinfunction "C_C") (pintype "passive"))
      (node (ref "IC12") (pin "14") (pinfunction "CLR_14") (pintype "bidirectional"))
      (node (ref "R46") (pin "P$1") (pinfunction "1_P$1") (pintype "passive"))
    )
    (net (code "66") (name "Net-(IC12-QA)") (class "Default")
      (node (ref "IC12") (pin "3") (pinfunction "QA_3") (pintype "bidirectional"))
      (node (ref "IC14") (pin "5") (pinfunction "0001_5") (pintype "input"))
    )
    (net (code "67") (name "Net-(IC12-QB)") (class "Default")
      (node (ref "IC12") (pin "2") (pinfunction "QB_2") (pintype "bidirectional"))
      (node (ref "IC14") (pin "3") (pinfunction "0010_3") (pintype "input"))
      (node (ref "IC8") (pin "2") (pinfunction "I1_2") (pintype "input"))
      (node (ref "IC8") (pin "4") (pinfunction "I0_4") (pintype "input"))
    )
    (net (code "68") (name "Net-(IC12-QC)") (class "Default")
      (node (ref "IC12") (pin "6") (pinfunction "QC_6") (pintype "bidirectional"))
      (node (ref "IC14") (pin "2") (pinfunction "0100_2") (pintype "input"))
    )
    (net (code "69") (name "Net-(IC12-QD)") (class "Default")
      (node (ref "IC12") (pin "7") (pinfunction "QD_7") (pintype "bidirectional"))
      (node (ref "IC14") (pin "4") (pinfunction "1000_4") (pintype "bidirectional"))
      (node (ref "IC8") (pin "1") (pinfunction "I0_1") (pintype "input"))
    )
    (net (code "70") (name "Net-(IC14-A)") (class "Default")
      (node (ref "IC14") (pin "9") (pinfunction "A_9") (pintype "bidirectional"))
      (node (ref "R32") (pin "P$1") (pinfunction "1_P$1") (pintype "passive"))
    )
    (net (code "71") (name "Net-(IC14-B)") (class "Default")
      (node (ref "IC14") (pin "10") (pinfunction "B_10") (pintype "bidirectional"))
      (node (ref "R33") (pin "P$1") (pinfunction "1_P$1") (pintype "passive"))
    )
    (net (code "72") (name "Net-(IC14-C)") (class "Default")
      (node (ref "IC14") (pin "11") (pinfunction "C_11") (pintype "bidirectional"))
      (node (ref "R34") (pin "P$1") (pinfunction "1_P$1") (pintype "passive"))
    )
    (net (code "73") (name "Net-(IC14-D)") (class "Default")
      (node (ref "IC14") (pin "12") (pinfunction "D_12") (pintype "bidirectional"))
      (node (ref "R35") (pin "P$1") (pinfunction "1_P$1") (pintype "passive"))
    )
    (net (code "74") (name "Net-(IC14-E)") (class "Default")
      (node (ref "IC14") (pin "13") (pinfunction "E_13") (pintype "bidirectional"))
      (node (ref "R36") (pin "P$1") (pinfunction "1_P$1") (pintype "passive"))
    )
    (net (code "75") (name "Net-(IC14-F)") (class "Default")
      (node (ref "IC14") (pin "15") (pinfunction "F_15") (pintype "bidirectional"))
      (node (ref "R37") (pin "P$1") (pinfunction "1_P$1") (pintype "passive"))
    )
    (net (code "76") (name "Net-(IC14-G)") (class "Default")
      (node (ref "IC14") (pin "14") (pinfunction "G_14") (pintype "bidirectional"))
      (node (ref "R38") (pin "P$1") (pinfunction "1_P$1") (pintype "passive"))
    )
    (net (code "77") (name "Net-(IC15-CLR)") (class "Default")
      (node (ref "D1") (pin "A") (pinfunction "A_A") (pintype "passive"))
      (node (ref "IC15") (pin "14") (pinfunction "CLR_14") (pintype "bidirectional"))
      (node (ref "IC8") (pin "6") (pinfunction "O_6") (pintype "output"))
    )
    (net (code "78") (name "Net-(IC15-QA)") (class "Default")
      (node (ref "IC15") (pin "3") (pinfunction "QA_3") (pintype "bidirectional"))
      (node (ref "IC16") (pin "5") (pinfunction "0001_5") (pintype "input"))
      (node (ref "IC8") (pin "5") (pinfunction "I1_5") (pintype "input"))
    )
    (net (code "79") (name "Net-(IC15-QB)") (class "Default")
      (node (ref "IC15") (pin "2") (pinfunction "QB_2") (pintype "bidirectional"))
      (node (ref "IC16") (pin "3") (pinfunction "0010_3") (pintype "input"))
    )
    (net (code "80") (name "Net-(IC15-QC)") (class "Default")
      (node (ref "IC15") (pin "6") (pinfunction "QC_6") (pintype "bidirectional"))
      (node (ref "IC16") (pin "2") (pinfunction "0100_2") (pintype "input"))
    )
    (net (code "81") (name "Net-(IC15-QD)") (class "Default")
      (node (ref "IC15") (pin "7") (pinfunction "QD_7") (pintype "bidirectional"))
      (node (ref "IC16") (pin "4") (pinfunction "1000_4") (pintype "bidirectional"))
    )
    (net (code "82") (name "Net-(IC15-UP)") (class "Default")
      (node (ref "D2") (pin "A") (pinfunction "A_A") (pintype "passive"))
      (node (ref "IC15") (pin "5") (pinfunction "UP_5") (pintype "bidirectional"))
      (node (ref "IC8") (pin "3") (pinfunction "O_3") (pintype "output"))
    )
    (net (code "83") (name "Net-(IC16-A)") (class "Default")
      (node (ref "IC16") (pin "9") (pinfunction "A_9") (pintype "bidirectional"))
      (node (ref "R39") (pin "P$1") (pinfunction "1_P$1") (pintype "passive"))
    )
    (net (code "84") (name "Net-(IC16-B)") (class "Default")
      (node (ref "IC16") (pin "10") (pinfunction "B_10") (pintype "bidirectional"))
      (node (ref "R40") (pin "P$1") (pinfunction "1_P$1") (pintype "passive"))
    )
    (net (code "85") (name "Net-(IC16-C)") (class "Default")
      (node (ref "IC16") (pin "11") (pinfunction "C_11") (pintype "bidirectional"))
      (node (ref "R41") (pin "P$1") (pinfunction "1_P$1") (pintype "passive"))
    )
    (net (code "86") (name "Net-(IC16-D)") (class "Default")
      (node (ref "IC16") (pin "12") (pinfunction "D_12") (pintype "bidirectional"))
      (node (ref "R42") (pin "P$1") (pinfunction "1_P$1") (pintype "passive"))
    )
    (net (code "87") (name "Net-(IC16-E)") (class "Default")
      (node (ref "IC16") (pin "13") (pinfunction "E_13") (pintype "bidirectional"))
      (node (ref "R43") (pin "P$1") (pinfunction "1_P$1") (pintype "passive"))
    )
    (net (code "88") (name "Net-(IC16-F)") (class "Default")
      (node (ref "IC16") (pin "15") (pinfunction "F_15") (pintype "bidirectional"))
      (node (ref "R44") (pin "P$1") (pinfunction "1_P$1") (pintype "passive"))
    )
    (net (code "89") (name "Net-(IC16-G)") (class "Default")
      (node (ref "IC16") (pin "14") (pinfunction "G_14") (pintype "bidirectional"))
      (node (ref "R45") (pin "P$1") (pinfunction "1_P$1") (pintype "passive"))
    )
    (net (code "90") (name "Net-(M_0X-B)") (class "Default")
      (node (ref "M_0X") (pin "P$9") (pinfunction "B_P$9") (pintype "passive"))
      (node (ref "R19") (pin "P$2") (pinfunction "2_P$2") (pintype "passive"))
    )
    (net (code "91") (name "Net-(M_0X-C)") (class "Default")
      (node (ref "M_0X") (pin "P$8") (pinfunction "C_P$8") (pintype "passive"))
      (node (ref "R20") (pin "P$2") (pinfunction "2_P$2") (pintype "passive"))
    )
    (net (code "92") (name "Net-(M_0X-D)") (class "Default")
      (node (ref "M_0X") (pin "P$5") (pinfunction "D_P$5") (pintype "passive"))
      (node (ref "R21") (pin "P$2") (pinfunction "2_P$2") (pintype "passive"))
    )
    (net (code "93") (name "Net-(M_0X-E)") (class "Default")
      (node (ref "M_0X") (pin "P$4") (pinfunction "E_P$4") (pintype "passive"))
      (node (ref "R22") (pin "P$2") (pinfunction "2_P$2") (pintype "passive"))
    )
    (net (code "94") (name "Net-(M_0X-F)") (class "Default")
      (node (ref "M_0X") (pin "P$2") (pinfunction "F_P$2") (pintype "passive"))
      (node (ref "R23") (pin "P$2") (pinfunction "2_P$2") (pintype "passive"))
    )
    (net (code "95") (name "Net-(M_0X-G)") (class "Default")
      (node (ref "M_0X") (pin "P$3") (pinfunction "G_P$3") (pintype "passive"))
      (node (ref "R24") (pin "P$2") (pinfunction "2_P$2") (pintype "passive"))
    )
    (net (code "96") (name "Net-(M_X0-B)") (class "Default")
      (node (ref "M_X0") (pin "P$9") (pinfunction "B_P$9") (pintype "passive"))
      (node (ref "R26") (pin "P$2") (pinfunction "2_P$2") (pintype "passive"))
    )
    (net (code "97") (name "Net-(M_X0-C)") (class "Default")
      (node (ref "M_X0") (pin "P$8") (pinfunction "C_P$8") (pintype "passive"))
      (node (ref "R27") (pin "P$2") (pinfunction "2_P$2") (pintype "passive"))
    )
    (net (code "98") (name "Net-(M_X0-D)") (class "Default")
      (node (ref "M_X0") (pin "P$5") (pinfunction "D_P$5") (pintype "passive"))
      (node (ref "R28") (pin "P$2") (pinfunction "2_P$2") (pintype "passive"))
    )
    (net (code "99") (name "Net-(M_X0-E)") (class "Default")
      (node (ref "M_X0") (pin "P$4") (pinfunction "E_P$4") (pintype "passive"))
      (node (ref "R29") (pin "P$2") (pinfunction "2_P$2") (pintype "passive"))
    )
    (net (code "100") (name "Net-(M_X0-F)") (class "Default")
      (node (ref "M_X0") (pin "P$2") (pinfunction "F_P$2") (pintype "passive"))
      (node (ref "R30") (pin "P$2") (pinfunction "2_P$2") (pintype "passive"))
    )
    (net (code "101") (name "Net-(M_X0-G)") (class "Default")
      (node (ref "M_X0") (pin "P$3") (pinfunction "G_P$3") (pintype "passive"))
      (node (ref "R31") (pin "P$2") (pinfunction "2_P$2") (pintype "passive"))
    )
    (net (code "102") (name "Net-(R1-2)") (class "Default")
      (node (ref "R1") (pin "P$2") (pinfunction "2_P$2") (pintype "passive"))
      (node (ref "R10") (pin "P$1") (pinfunction "1_P$1") (pintype "passive"))
    )
    (net (code "103") (name "Net-(R2-2)") (class "Default")
      (node (ref "R2") (pin "P$2") (pinfunction "2_P$2") (pintype "passive"))
      (node (ref "S_0X") (pin "P$10") (pinfunction "A_P$10") (pintype "passive"))
    )
    (net (code "104") (name "Net-(R3-2)") (class "Default")
      (node (ref "R3") (pin "P$2") (pinfunction "2_P$2") (pintype "passive"))
      (node (ref "S_0X") (pin "P$9") (pinfunction "B_P$9") (pintype "passive"))
    )
    (net (code "105") (name "Net-(R4-2)") (class "Default")
      (node (ref "R4") (pin "P$2") (pinfunction "2_P$2") (pintype "passive"))
      (node (ref "S_0X") (pin "P$8") (pinfunction "C_P$8") (pintype "passive"))
    )
    (net (code "106") (name "Net-(R5-2)") (class "Default")
      (node (ref "R5") (pin "P$2") (pinfunction "2_P$2") (pintype "passive"))
      (node (ref "S_0X") (pin "P$5") (pinfunction "D_P$5") (pintype "passive"))
    )
    (net (code "107") (name "Net-(R6-2)") (class "Default")
      (node (ref "R6") (pin "P$2") (pinfunction "2_P$2") (pintype "passive"))
      (node (ref "S_0X") (pin "P$4") (pinfunction "E_P$4") (pintype "passive"))
    )
    (net (code "108") (name "Net-(R7-2)") (class "Default")
      (node (ref "R7") (pin "P$2") (pinfunction "2_P$2") (pintype "passive"))
      (node (ref "S_0X") (pin "P$2") (pinfunction "F_P$2") (pintype "passive"))
    )
    (net (code "109") (name "Net-(R8-2)") (class "Default")
      (node (ref "R8") (pin "P$2") (pinfunction "2_P$2") (pintype "passive"))
      (node (ref "S_0X") (pin "P$3") (pinfunction "G_P$3") (pintype "passive"))
    )
    (net (code "110") (name "Net-(R10-2)") (class "Default")
      (node (ref "R10") (pin "P$2") (pinfunction "2_P$2") (pintype "passive"))
      (node (ref "VR1") (pin "2") (pinfunction "S_2") (pintype "passive"))
    )
    (net (code "111") (name "Net-(R11-2)") (class "Default")
      (node (ref "R11") (pin "P$2") (pinfunction "2_P$2") (pintype "passive"))
      (node (ref "S_X0") (pin "P$10") (pinfunction "A_P$10") (pintype "passive"))
    )
    (net (code "112") (name "Net-(R12-2)") (class "Default")
      (node (ref "R12") (pin "P$2") (pinfunction "2_P$2") (pintype "passive"))
      (node (ref "S_X0") (pin "P$9") (pinfunction "B_P$9") (pintype "passive"))
    )
    (net (code "113") (name "Net-(R13-2)") (class "Default")
      (node (ref "R13") (pin "P$2") (pinfunction "2_P$2") (pintype "passive"))
      (node (ref "S_X0") (pin "P$8") (pinfunction "C_P$8") (pintype "passive"))
    )
    (net (code "114") (name "Net-(R14-2)") (class "Default")
      (node (ref "R14") (pin "P$2") (pinfunction "2_P$2") (pintype "passive"))
      (node (ref "S_X0") (pin "P$5") (pinfunction "D_P$5") (pintype "passive"))
    )
    (net (code "115") (name "Net-(R15-2)") (class "Default")
      (node (ref "R15") (pin "P$2") (pinfunction "2_P$2") (pintype "passive"))
      (node (ref "S_X0") (pin "P$4") (pinfunction "E_P$4") (pintype "passive"))
    )
    (net (code "116") (name "Net-(R16-2)") (class "Default")
      (node (ref "R16") (pin "P$2") (pinfunction "2_P$2") (pintype "passive"))
      (node (ref "S_X0") (pin "P$2") (pinfunction "F_P$2") (pintype "passive"))
    )
    (net (code "117") (name "Net-(R17-2)") (class "Default")
      (node (ref "R17") (pin "P$2") (pinfunction "2_P$2") (pintype "passive"))
      (node (ref "S_X0") (pin "P$3") (pinfunction "G_P$3") (pintype "passive"))
    )
    (net (code "118") (name "Net-(R18-2)") (class "Default")
      (node (ref "M_0X") (pin "P$10") (pinfunction "A_P$10") (pintype "passive"))
      (node (ref "R18") (pin "P$2") (pinfunction "2_P$2") (pintype "passive"))
    )
    (net (code "119") (name "Net-(R25-2)") (class "Default")
      (node (ref "M_X0") (pin "P$10") (pinfunction "A_P$10") (pintype "passive"))
      (node (ref "R25") (pin "P$2") (pinfunction "2_P$2") (pintype "passive"))
    )
    (net (code "120") (name "Net-(R32-2)") (class "Default")
      (node (ref "H_0X") (pin "P$10") (pinfunction "A_P$10") (pintype "passive"))
      (node (ref "R32") (pin "P$2") (pinfunction "2_P$2") (pintype "passive"))
    )
    (net (code "121") (name "Net-(R39-2)") (class "Default")
      (node (ref "H_X0") (pin "P$10") (pinfunction "A_P$10") (pintype "passive"))
      (node (ref "R39") (pin "P$2") (pinfunction "2_P$2") (pintype "passive"))
    )
    (net (code "122") (name "SEC_MAJOR_C") (class "Default")
      (node (ref "IC1") (pin "6") (pinfunction "O_6") (pintype "output"))
      (node (ref "IC6") (pin "14") (pinfunction "CLR_14") (pintype "bidirectional"))
      (node (ref "IC7") (pin "5") (pinfunction "UP_5") (pintype "bidirectional"))
    )
    (net (code "123") (name "SINK_UNDEFINED") (class "Default")
      (node (ref "C10") (pin "1") (pinfunction "1_1") (pintype "passive"))
      (node (ref "C11") (pin "1") (pinfunction "1_1") (pintype "passive"))
      (node (ref "C12") (pin "1") (pinfunction "1_1") (pintype "passive"))
      (node (ref "C13") (pin "1") (pinfunction "1_1") (pintype "passive"))
      (node (ref "C14") (pin "1") (pinfunction "1_1") (pintype "passive"))
      (node (ref "C15") (pin "1") (pinfunction "1_1") (pintype "passive"))
      (node (ref "C16") (pin "1") (pinfunction "1_1") (pintype "passive"))
      (node (ref "C17") (pin "1") (pinfunction "1_1") (pintype "passive"))
      (node (ref "C3") (pin "1") (pinfunction "1_1") (pintype "passive"))
      (node (ref "C4") (pin "1") (pinfunction "1_1") (pintype "passive"))
      (node (ref "C5") (pin "1") (pinfunction "1_1") (pintype "passive"))
      (node (ref "C6") (pin "1") (pinfunction "1_1") (pintype "passive"))
      (node (ref "C7") (pin "1") (pinfunction "1_1") (pintype "passive"))
      (node (ref "C8") (pin "1") (pinfunction "1_1") (pintype "passive"))
      (node (ref "C9") (pin "1") (pinfunction "1_1") (pintype "passive"))
      (node (ref "H_0X") (pin "P$1") (pinfunction "A_P$1") (pintype "passive"))
      (node (ref "H_0X") (pin "P$6") (pinfunction "A_P$6") (pintype "passive"))
      (node (ref "H_X0") (pin "P$1") (pinfunction "A_P$1") (pintype "passive"))
      (node (ref "H_X0") (pin "P$6") (pinfunction "A_P$6") (pintype "passive"))
      (node (ref "IC10") (pin "11") (pinfunction "LOAD_11") (pintype "input"))
      (node (ref "IC10") (pin "12") (pinfunction "CO_12") (pintype "input"))
      (node (ref "IC10") (pin "13") (pinfunction "BO_13") (pintype "bidirectional"))
      (node (ref "IC10") (pin "16") (pinfunction "VCC_16") (pintype "power_in"))
      (node (ref "IC10") (pin "4") (pinfunction "DOWN_4") (pintype "input"))
      (node (ref "IC11") (pin "16") (pinfunction "VDD_16") (pintype "power_in"))
      (node (ref "IC11") (pin "6") (pinfunction "FREQ_6") (pintype "bidirectional"))
      (node (ref "IC12") (pin "11") (pinfunction "LOAD_11") (pintype "input"))
      (node (ref "IC12") (pin "12") (pinfunction "CO_12") (pintype "input"))
      (node (ref "IC12") (pin "13") (pinfunction "BO_13") (pintype "bidirectional"))
      (node (ref "IC12") (pin "16") (pinfunction "VCC_16") (pintype "power_in"))
      (node (ref "IC12") (pin "4") (pinfunction "DOWN_4") (pintype "input"))
      (node (ref "IC14") (pin "16") (pinfunction "VDD_16") (pintype "power_in"))
      (node (ref "IC14") (pin "6") (pinfunction "FREQ_6") (pintype "bidirectional"))
      (node (ref "IC15") (pin "11") (pinfunction "LOAD_11") (pintype "input"))
      (node (ref "IC15") (pin "12") (pinfunction "CO_12") (pintype "input"))
      (node (ref "IC15") (pin "13") (pinfunction "BO_13") (pintype "bidirectional"))
      (node (ref "IC15") (pin "16") (pinfunction "VCC_16") (pintype "power_in"))
      (node (ref "IC15") (pin "4") (pinfunction "DOWN_4") (pintype "input"))
      (node (ref "IC16") (pin "16") (pinfunction "VDD_16") (pintype "power_in"))
      (node (ref "IC16") (pin "6") (pinfunction "FREQ_6") (pintype "bidirectional"))
      (node (ref "IC2") (pin "4") (pinfunction "/RES_4") (pintype "input"))
      (node (ref "IC2") (pin "8") (pinfunction "VCC+_8") (pintype "power_in"))
      (node (ref "IC3") (pin "11") (pinfunction "LOAD_11") (pintype "input"))
      (node (ref "IC3") (pin "12") (pinfunction "CO_12") (pintype "input"))
      (node (ref "IC3") (pin "13") (pinfunction "BO_13") (pintype "bidirectional"))
      (node (ref "IC3") (pin "16") (pinfunction "VCC_16") (pintype "power_in"))
      (node (ref "IC3") (pin "4") (pinfunction "DOWN_4") (pintype "input"))
      (node (ref "IC4") (pin "16") (pinfunction "VDD_16") (pintype "power_in"))
      (node (ref "IC4") (pin "6") (pinfunction "FREQ_6") (pintype "bidirectional"))
      (node (ref "IC5") (pin "16") (pinfunction "VDD_16") (pintype "power_in"))
      (node (ref "IC5") (pin "6") (pinfunction "FREQ_6") (pintype "bidirectional"))
      (node (ref "IC6") (pin "11") (pinfunction "LOAD_11") (pintype "input"))
      (node (ref "IC6") (pin "12") (pinfunction "CO_12") (pintype "input"))
      (node (ref "IC6") (pin "13") (pinfunction "BO_13") (pintype "bidirectional"))
      (node (ref "IC6") (pin "16") (pinfunction "VCC_16") (pintype "power_in"))
      (node (ref "IC6") (pin "4") (pinfunction "DOWN_4") (pintype "input"))
      (node (ref "IC7") (pin "11") (pinfunction "LOAD_11") (pintype "input"))
      (node (ref "IC7") (pin "12") (pinfunction "CO_12") (pintype "input"))
      (node (ref "IC7") (pin "13") (pinfunction "BO_13") (pintype "bidirectional"))
      (node (ref "IC7") (pin "16") (pinfunction "VCC_16") (pintype "power_in"))
      (node (ref "IC7") (pin "4") (pinfunction "DOWN_4") (pintype "input"))
      (node (ref "IC9") (pin "16") (pinfunction "VDD_16") (pintype "power_in"))
      (node (ref "IC9") (pin "6") (pinfunction "FREQ_6") (pintype "bidirectional"))
      (node (ref "JP1") (pin "2") (pinfunction "2_2") (pintype "passive"))
      (node (ref "M_0X") (pin "P$1") (pinfunction "A_P$1") (pintype "passive"))
      (node (ref "M_0X") (pin "P$6") (pinfunction "A_P$6") (pintype "passive"))
      (node (ref "M_X0") (pin "P$1") (pinfunction "A_P$1") (pintype "passive"))
      (node (ref "M_X0") (pin "P$6") (pinfunction "A_P$6") (pintype "passive"))
      (node (ref "S_0X") (pin "P$1") (pinfunction "A_P$1") (pintype "passive"))
      (node (ref "S_0X") (pin "P$6") (pinfunction "A_P$6") (pintype "passive"))
      (node (ref "S_X0") (pin "P$1") (pinfunction "A_P$1") (pintype "passive"))
      (node (ref "S_X0") (pin "P$6") (pinfunction "A_P$6") (pintype "passive"))
    )
    (net (code "124") (name "unconnected-(H_0X-DP-PadP$7)") (class "Default")
      (node (ref "H_0X") (pin "P$7") (pinfunction "DP_P$7") (pintype "passive"))
    )
    (net (code "125") (name "unconnected-(H_X0-DP-PadP$7)") (class "Default")
      (node (ref "H_X0") (pin "P$7") (pinfunction "DP_P$7") (pintype "passive"))
    )
    (net (code "126") (name "unconnected-(IC2-DIS-Pad7)") (class "Default")
      (node (ref "IC2") (pin "7") (pinfunction "DIS_7") (pintype "input"))
    )
    (net (code "127") (name "unconnected-(IC3-A-Pad15)") (class "Default")
      (node (ref "IC3") (pin "15") (pinfunction "A_15") (pintype "bidirectional"))
    )
    (net (code "128") (name "unconnected-(IC3-B-Pad1)") (class "Default")
      (node (ref "IC3") (pin "1") (pinfunction "B_1") (pintype "bidirectional"))
    )
    (net (code "129") (name "unconnected-(IC3-C-Pad10)") (class "Default")
      (node (ref "IC3") (pin "10") (pinfunction "C_10") (pintype "bidirectional"))
    )
    (net (code "130") (name "unconnected-(IC3-D-Pad9)") (class "Default")
      (node (ref "IC3") (pin "9") (pinfunction "D_9") (pintype "bidirectional"))
    )
    (net (code "131") (name "unconnected-(IC4-STRB-Pad1)") (class "Default")
      (node (ref "IC4") (pin "1") (pinfunction "STRB_1") (pintype "bidirectional"))
    )
    (net (code "132") (name "unconnected-(IC5-STRB-Pad1)") (class "Default")
      (node (ref "IC5") (pin "1") (pinfunction "STRB_1") (pintype "bidirectional"))
    )
    (net (code "133") (name "unconnected-(IC6-A-Pad15)") (class "Default")
      (node (ref "IC6") (pin "15") (pinfunction "A_15") (pintype "bidirectional"))
    )
    (net (code "134") (name "unconnected-(IC6-B-Pad1)") (class "Default")
      (node (ref "IC6") (pin "1") (pinfunction "B_1") (pintype "bidirectional"))
    )
    (net (code "135") (name "unconnected-(IC6-C-Pad10)") (class "Default")
      (node (ref "IC6") (pin "10") (pinfunction "C_10") (pintype "bidirectional"))
    )
    (net (code "136") (name "unconnected-(IC6-D-Pad9)") (class "Default")
      (node (ref "IC6") (pin "9") (pinfunction "D_9") (pintype "bidirectional"))
    )
    (net (code "137") (name "unconnected-(IC7-A-Pad15)") (class "Default")
      (node (ref "IC7") (pin "15") (pinfunction "A_15") (pintype "bidirectional"))
    )
    (net (code "138") (name "unconnected-(IC7-B-Pad1)") (class "Default")
      (node (ref "IC7") (pin "1") (pinfunction "B_1") (pintype "bidirectional"))
    )
    (net (code "139") (name "unconnected-(IC7-C-Pad10)") (class "Default")
      (node (ref "IC7") (pin "10") (pinfunction "C_10") (pintype "bidirectional"))
    )
    (net (code "140") (name "unconnected-(IC7-D-Pad9)") (class "Default")
      (node (ref "IC7") (pin "9") (pinfunction "D_9") (pintype "bidirectional"))
    )
    (net (code "141") (name "unconnected-(IC9-STRB-Pad1)") (class "Default")
      (node (ref "IC9") (pin "1") (pinfunction "STRB_1") (pintype "bidirectional"))
    )
    (net (code "142") (name "unconnected-(IC10-A-Pad15)") (class "Default")
      (node (ref "IC10") (pin "15") (pinfunction "A_15") (pintype "bidirectional"))
    )
    (net (code "143") (name "unconnected-(IC10-B-Pad1)") (class "Default")
      (node (ref "IC10") (pin "1") (pinfunction "B_1") (pintype "bidirectional"))
    )
    (net (code "144") (name "unconnected-(IC10-C-Pad10)") (class "Default")
      (node (ref "IC10") (pin "10") (pinfunction "C_10") (pintype "bidirectional"))
    )
    (net (code "145") (name "unconnected-(IC10-D-Pad9)") (class "Default")
      (node (ref "IC10") (pin "9") (pinfunction "D_9") (pintype "bidirectional"))
    )
    (net (code "146") (name "unconnected-(IC11-STRB-Pad1)") (class "Default")
      (node (ref "IC11") (pin "1") (pinfunction "STRB_1") (pintype "bidirectional"))
    )
    (net (code "147") (name "unconnected-(IC12-A-Pad15)") (class "Default")
      (node (ref "IC12") (pin "15") (pinfunction "A_15") (pintype "bidirectional"))
    )
    (net (code "148") (name "unconnected-(IC12-B-Pad1)") (class "Default")
      (node (ref "IC12") (pin "1") (pinfunction "B_1") (pintype "bidirectional"))
    )
    (net (code "149") (name "unconnected-(IC12-C-Pad10)") (class "Default")
      (node (ref "IC12") (pin "10") (pinfunction "C_10") (pintype "bidirectional"))
    )
    (net (code "150") (name "unconnected-(IC12-D-Pad9)") (class "Default")
      (node (ref "IC12") (pin "9") (pinfunction "D_9") (pintype "bidirectional"))
    )
    (net (code "151") (name "unconnected-(IC14-STRB-Pad1)") (class "Default")
      (node (ref "IC14") (pin "1") (pinfunction "STRB_1") (pintype "bidirectional"))
    )
    (net (code "152") (name "unconnected-(IC15-A-Pad15)") (class "Default")
      (node (ref "IC15") (pin "15") (pinfunction "A_15") (pintype "bidirectional"))
    )
    (net (code "153") (name "unconnected-(IC15-B-Pad1)") (class "Default")
      (node (ref "IC15") (pin "1") (pinfunction "B_1") (pintype "bidirectional"))
    )
    (net (code "154") (name "unconnected-(IC15-C-Pad10)") (class "Default")
      (node (ref "IC15") (pin "10") (pinfunction "C_10") (pintype "bidirectional"))
    )
    (net (code "155") (name "unconnected-(IC15-D-Pad9)") (class "Default")
      (node (ref "IC15") (pin "9") (pinfunction "D_9") (pintype "bidirectional"))
    )
    (net (code "156") (name "unconnected-(IC16-STRB-Pad1)") (class "Default")
      (node (ref "IC16") (pin "1") (pinfunction "STRB_1") (pintype "bidirectional"))
    )
    (net (code "157") (name "unconnected-(M_0X-DP-PadP$7)") (class "Default")
      (node (ref "M_0X") (pin "P$7") (pinfunction "DP_P$7") (pintype "passive"))
    )
    (net (code "158") (name "unconnected-(M_X0-DP-PadP$7)") (class "Default")
      (node (ref "M_X0") (pin "P$7") (pinfunction "DP_P$7") (pintype "passive"))
    )
    (net (code "159") (name "unconnected-(S_0X-DP-PadP$7)") (class "Default")
      (node (ref "S_0X") (pin "P$7") (pinfunction "DP_P$7") (pintype "passive"))
    )
    (net (code "160") (name "unconnected-(S_X0-DP-PadP$7)") (class "Default")
      (node (ref "S_X0") (pin "P$7") (pinfunction "DP_P$7") (pintype "passive"))
    )
    (net (code "161") (name "unconnected-(VR1-E-Pad3)") (class "Default")
      (node (ref "VR1") (pin "3") (pinfunction "E_3") (pintype "passive"))
    )
  )
)
